# top.net
KiCad netlist of a schematic drawn in EAGLE
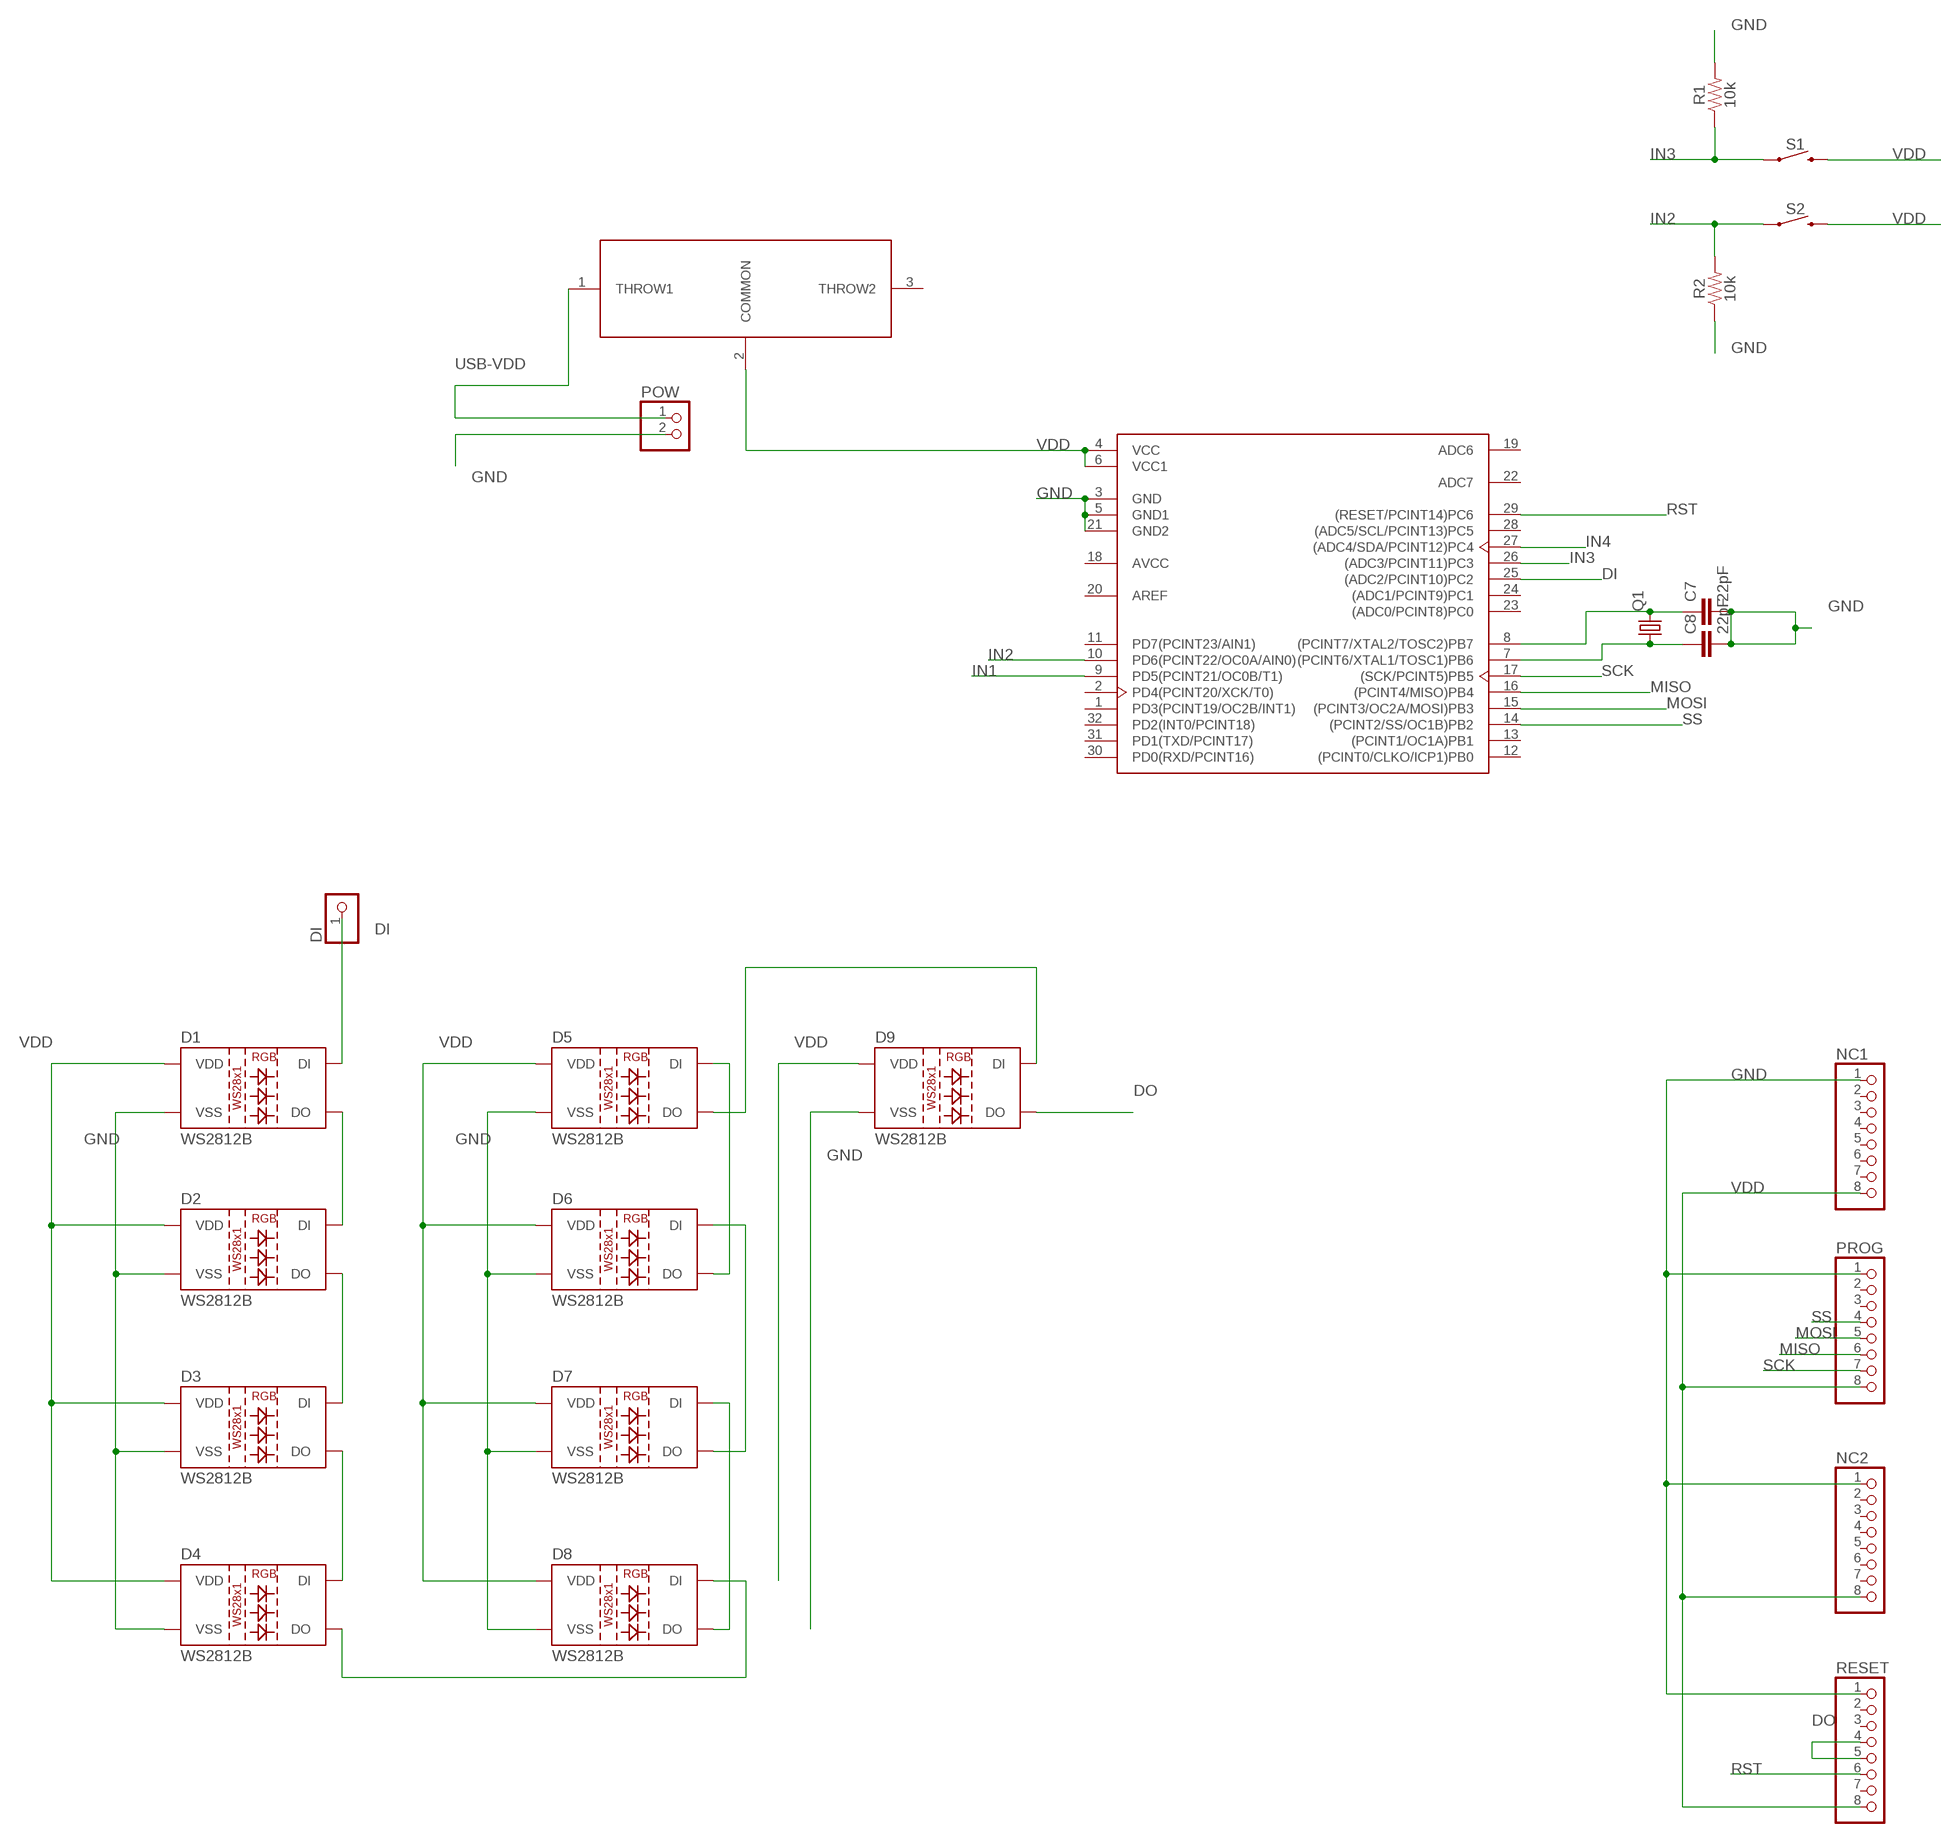
[diagram p0: schematic, sheet 1]

(export (version "E")
  (design (tool "Eeschema 10.0.6"))
  (components
    (comp (ref "C7")
      (value "22pF")
      (footprint "eagle-import:0805")
      (libsource (lib "eagle-import") (part "1.0UF-0805-25V-(+80/-20%)"))
    )
    (comp (ref "C8")
      (value "22pF")
      (footprint "eagle-import:0805")
      (libsource (lib "eagle-import") (part "1.0UF-0805-25V-(+80/-20%)"))
    )
    (comp (ref "D1")
      (value "WS2812B")
      (footprint "eagle-import:WS2812B")
      (libsource (lib "eagle-import") (part "WS2812B"))
    )
    (comp (ref "D2")
      (value "WS2812B")
      (footprint "eagle-import:WS2812B")
      (libsource (lib "eagle-import") (part "WS2812B"))
    )
    (comp (ref "D3")
      (value "WS2812B")
      (footprint "eagle-import:WS2812B")
      (libsource (lib "eagle-import") (part "WS2812B"))
    )
    (comp (ref "D4")
      (value "WS2812B")
      (footprint "eagle-import:WS2812B")
      (libsource (lib "eagle-import") (part "WS2812B"))
    )
    (comp (ref "D5")
      (value "WS2812B")
      (footprint "eagle-import:WS2812B")
      (libsource (lib "eagle-import") (part "WS2812B"))
    )
    (comp (ref "D6")
      (value "WS2812B")
      (footprint "eagle-import:WS2812B")
      (libsource (lib "eagle-import") (part "WS2812B"))
    )
    (comp (ref "D7")
      (value "WS2812B")
      (footprint "eagle-import:WS2812B")
      (libsource (lib "eagle-import") (part "WS2812B"))
    )
    (comp (ref "D8")
      (value "WS2812B")
      (footprint "eagle-import:WS2812B")
      (libsource (lib "eagle-import") (part "WS2812B"))
    )
    (comp (ref "D9")
      (value "WS2812B")
      (footprint "eagle-import:WS2812B")
      (libsource (lib "eagle-import") (part "WS2812B"))
    )
    (comp (ref "DI")
      (value "PINHD-1X1")
      (footprint "eagle-import:1X01")
      (libsource (lib "eagle-import") (part "PINHD-1X1"))
    )
    (comp (ref "IC1")
      (value "ATMEGA328P-AU")
      (footprint "eagle-import:TQFP-32")
      (fields
        (field (name "DIGIKEY_PART_NUMBER") "ATMEGA328P-AU-ND")
        (field (name "MANUFACTURER") "Microchip Technology")
        (field (name "CREATED_BY") "PCBLayout.com")
      )
      (libsource (lib "eagle-import") (part "ATMEGA328P-AU"))
    )
    (comp (ref "NC1")
      (value "PINHD-1X8")
      (footprint "eagle-import:1X08")
      (libsource (lib "eagle-import") (part "PINHD-1X8"))
    )
    (comp (ref "NC2")
      (value "PINHD-1X8")
      (footprint "eagle-import:1X08")
      (libsource (lib "eagle-import") (part "PINHD-1X8"))
    )
    (comp (ref "POW")
      (value "PINHD-1X2")
      (footprint "eagle-import:1X02")
      (libsource (lib "eagle-import") (part "PINHD-1X2"))
    )
    (comp (ref "PROG")
      (value "PINHD-1X8")
      (footprint "eagle-import:1X08")
      (libsource (lib "eagle-import") (part "PINHD-1X8"))
    )
    (comp (ref "Q1")
      (value "CRYSTALHC49S")
      (footprint "eagle-import:HC49_S")
      (libsource (lib "eagle-import") (part "CRYSTALHC49S"))
    )
    (comp (ref "R1")
      (value "10k")
      (footprint "eagle-import:0805")
      (libsource (lib "eagle-import") (part "0.3OHM-0805-1/8W-1%"))
    )
    (comp (ref "R2")
      (value "10k")
      (footprint "eagle-import:0805")
      (libsource (lib "eagle-import") (part "0.3OHM-0805-1/8W-1%"))
    )
    (comp (ref "RESET")
      (value "PINHD-1X8")
      (footprint "eagle-import:1X08")
      (libsource (lib "eagle-import") (part "PINHD-1X8"))
    )
    (comp (ref "S1")
      (value "MOMENTARY-SWITCH-SPST-PTH-6.0MM")
      (footprint "eagle-import:TACTILE_SWITCH_PTH_6.0MM")
      (libsource (lib "eagle-import") (part "MOMENTARY-SWITCH-SPST-PTH-6.0MM"))
    )
    (comp (ref "S2")
      (value "MOMENTARY-SWITCH-SPST-PTH-6.0MM")
      (footprint "eagle-import:TACTILE_SWITCH_PTH_6.0MM")
      (libsource (lib "eagle-import") (part "MOMENTARY-SWITCH-SPST-PTH-6.0MM"))
    )
    (comp (ref "U$2")
      (value "SLIDE_SWITCH_1P2T")
      (footprint "eagle-import:SLIDE_SWITCH_1P2T")
      (libsource (lib "eagle-import") (part "SLIDE_SWITCH_1P2T"))
    )
  )
  (nets
    (net (code "1") (name "/AREF") (class "Default")
      (node (ref "IC1") (pin "20") (pinfunction "AREF_20") (pintype "power_in"))
    )
    (net (code "2") (name "/AVCC") (class "Default")
      (node (ref "IC1") (pin "18") (pinfunction "AVCC_18") (pintype "power_in"))
    )
    (net (code "3") (name "/DI") (class "Default")
      (node (ref "D1") (pin "4") (pinfunction "DI_4") (pintype "bidirectional"))
      (node (ref "DI") (pin "1") (pinfunction "1_1") (pintype "passive"))
      (node (ref "IC1") (pin "25") (pinfunction "(ADC2/PCINT10)PC2_25") (pintype "bidirectional"))
    )
    (net (code "4") (name "/DO") (class "Default")
      (node (ref "D9") (pin "2") (pinfunction "DO_2") (pintype "bidirectional"))
      (node (ref "RESET") (pin "4") (pinfunction "4_4") (pintype "passive"))
      (node (ref "RESET") (pin "5") (pinfunction "5_5") (pintype "passive"))
    )
    (net (code "5") (name "/GND") (class "Default")
      (node (ref "C7") (pin "2") (pinfunction "2_2") (pintype "passive"))
      (node (ref "C8") (pin "2") (pinfunction "2_2") (pintype "passive"))
      (node (ref "D1") (pin "3") (pinfunction "VSS_3") (pintype "bidirectional"))
      (node (ref "D2") (pin "3") (pinfunction "VSS_3") (pintype "bidirectional"))
      (node (ref "D3") (pin "3") (pinfunction "VSS_3") (pintype "bidirectional"))
      (node (ref "D4") (pin "3") (pinfunction "VSS_3") (pintype "bidirectional"))
      (node (ref "D5") (pin "3") (pinfunction "VSS_3") (pintype "bidirectional"))
      (node (ref "D6") (pin "3") (pinfunction "VSS_3") (pintype "bidirectional"))
      (node (ref "D7") (pin "3") (pinfunction "VSS_3") (pintype "bidirectional"))
      (node (ref "D8") (pin "3") (pinfunction "VSS_3") (pintype "bidirectional"))
      (node (ref "D9") (pin "3") (pinfunction "VSS_3") (pintype "bidirectional"))
      (node (ref "IC1") (pin "21") (pinfunction "GND2_21") (pintype "power_in"))
      (node (ref "IC1") (pin "3") (pinfunction "GND_3") (pintype "power_in"))
      (node (ref "IC1") (pin "5") (pinfunction "GND1_5") (pintype "power_in"))
      (node (ref "NC1") (pin "1") (pinfunction "1_1") (pintype "passive"))
      (node (ref "NC2") (pin "1") (pinfunction "1_1") (pintype "passive"))
      (node (ref "POW") (pin "2") (pinfunction "2_2") (pintype "passive"))
      (node (ref "PROG") (pin "1") (pinfunction "1_1") (pintype "passive"))
      (node (ref "R1") (pin "2") (pinfunction "2_2") (pintype "passive"))
      (node (ref "R2") (pin "1") (pinfunction "1_1") (pintype "passive"))
      (node (ref "RESET") (pin "1") (pinfunction "1_1") (pintype "passive"))
    )
    (net (code "6") (name "/IN1") (class "Default")
      (node (ref "IC1") (pin "9") (pinfunction "PD5(PCINT21/OC0B/T1)_9") (pintype "bidirectional"))
    )
    (net (code "7") (name "/IN2") (class "Default")
      (node (ref "IC1") (pin "10") (pinfunction "PD6(PCINT22/OC0A/AIN0)_10") (pintype "bidirectional"))
      (node (ref "R2") (pin "2") (pinfunction "2_2") (pintype "passive"))
      (node (ref "S2") (pin "1") (pinfunction "1_1") (pintype "passive"))
    )
    (net (code "8") (name "/IN3") (class "Default")
      (node (ref "IC1") (pin "26") (pinfunction "(ADC3/PCINT11)PC3_26") (pintype "bidirectional"))
      (node (ref "R1") (pin "1") (pinfunction "1_1") (pintype "passive"))
      (node (ref "S1") (pin "1") (pinfunction "1_1") (pintype "passive"))
    )
    (net (code "9") (name "/IN4") (class "Default")
      (node (ref "IC1") (pin "27") (pinfunction "(ADC4/SDA/PCINT12)PC4_27") (pintype "bidirectional"))
    )
    (net (code "10") (name "/MISO") (class "Default")
      (node (ref "IC1") (pin "16") (pinfunction "(PCINT4/MISO)PB4_16") (pintype "bidirectional"))
      (node (ref "PROG") (pin "6") (pinfunction "6_6") (pintype "passive"))
    )
    (net (code "11") (name "/MOSI") (class "Default")
      (node (ref "IC1") (pin "15") (pinfunction "(PCINT3/OC2A/MOSI)PB3_15") (pintype "bidirectional"))
      (node (ref "PROG") (pin "5") (pinfunction "5_5") (pintype "passive"))
    )
    (net (code "12") (name "/RST") (class "Default")
      (node (ref "IC1") (pin "29") (pinfunction "(RESET/PCINT14)PC6_29") (pintype "bidirectional"))
      (node (ref "RESET") (pin "6") (pinfunction "6_6") (pintype "passive"))
    )
    (net (code "13") (name "/SCK") (class "Default")
      (node (ref "IC1") (pin "17") (pinfunction "(SCK/PCINT5)PB5_17") (pintype "bidirectional"))
      (node (ref "PROG") (pin "7") (pinfunction "7_7") (pintype "passive"))
    )
    (net (code "14") (name "/SS") (class "Default")
      (node (ref "IC1") (pin "14") (pinfunction "(PCINT2/SS/OC1B)PB2_14") (pintype "bidirectional"))
      (node (ref "PROG") (pin "4") (pinfunction "4_4") (pintype "passive"))
    )
    (net (code "15") (name "/USB-VDD") (class "Default")
      (node (ref "POW") (pin "1") (pinfunction "1_1") (pintype "passive"))
      (node (ref "U$2") (pin "1") (pinfunction "THROW1_1") (pintype "bidirectional"))
    )
    (net (code "16") (name "/VDD") (class "Default")
      (node (ref "D1") (pin "1") (pinfunction "VDD_1") (pintype "bidirectional"))
      (node (ref "D2") (pin "1") (pinfunction "VDD_1") (pintype "bidirectional"))
      (node (ref "D3") (pin "1") (pinfunction "VDD_1") (pintype "bidirectional"))
      (node (ref "D4") (pin "1") (pinfunction "VDD_1") (pintype "bidirectional"))
      (node (ref "D5") (pin "1") (pinfunction "VDD_1") (pintype "bidirectional"))
      (node (ref "D6") (pin "1") (pinfunction "VDD_1") (pintype "bidirectional"))
      (node (ref "D7") (pin "1") (pinfunction "VDD_1") (pintype "bidirectional"))
      (node (ref "D8") (pin "1") (pinfunction "VDD_1") (pintype "bidirectional"))
      (node (ref "D9") (pin "1") (pinfunction "VDD_1") (pintype "bidirectional"))
      (node (ref "IC1") (pin "4") (pinfunction "VCC_4") (pintype "power_in"))
      (node (ref "IC1") (pin "6") (pinfunction "VCC1_6") (pintype "power_in"))
      (node (ref "NC1") (pin "8") (pinfunction "8_8") (pintype "passive"))
      (node (ref "NC2") (pin "8") (pinfunction "8_8") (pintype "passive"))
      (node (ref "PROG") (pin "8") (pinfunction "8_8") (pintype "passive"))
      (node (ref "RESET") (pin "8") (pinfunction "8_8") (pintype "passive"))
      (node (ref "S1") (pin "3") (pinfunction "2_3") (pintype "passive"))
      (node (ref "S2") (pin "3") (pinfunction "2_3") (pintype "passive"))
      (node (ref "U$2") (pin "2") (pinfunction "COMMON_2") (pintype "bidirectional"))
    )
    (net (code "17") (name "Net-(D1-DO)") (class "Default")
      (node (ref "D1") (pin "2") (pinfunction "DO_2") (pintype "bidirectional"))
      (node (ref "D2") (pin "4") (pinfunction "DI_4") (pintype "bidirectional"))
    )
    (net (code "18") (name "Net-(D2-DO)") (class "Default")
      (node (ref "D2") (pin "2") (pinfunction "DO_2") (pintype "bidirectional"))
      (node (ref "D3") (pin "4") (pinfunction "DI_4") (pintype "bidirectional"))
    )
    (net (code "19") (name "Net-(D3-DO)") (class "Default")
      (node (ref "D3") (pin "2") (pinfunction "DO_2") (pintype "bidirectional"))
      (node (ref "D4") (pin "4") (pinfunction "DI_4") (pintype "bidirectional"))
    )
    (net (code "20") (name "Net-(D4-DO)") (class "Default")
      (node (ref "D4") (pin "2") (pinfunction "DO_2") (pintype "bidirectional"))
      (node (ref "D8") (pin "4") (pinfunction "DI_4") (pintype "bidirectional"))
    )
    (net (code "21") (name "Net-(D5-DI)") (class "Default")
      (node (ref "D5") (pin "4") (pinfunction "DI_4") (pintype "bidirectional"))
      (node (ref "D6") (pin "2") (pinfunction "DO_2") (pintype "bidirectional"))
    )
    (net (code "22") (name "Net-(D5-DO)") (class "Default")
      (node (ref "D5") (pin "2") (pinfunction "DO_2") (pintype "bidirectional"))
      (node (ref "D9") (pin "4") (pinfunction "DI_4") (pintype "bidirectional"))
    )
    (net (code "23") (name "Net-(D6-DI)") (class "Default")
      (node (ref "D6") (pin "4") (pinfunction "DI_4") (pintype "bidirectional"))
      (node (ref "D7") (pin "2") (pinfunction "DO_2") (pintype "bidirectional"))
    )
    (net (code "24") (name "Net-(D7-DI)") (class "Default")
      (node (ref "D7") (pin "4") (pinfunction "DI_4") (pintype "bidirectional"))
      (node (ref "D8") (pin "2") (pinfunction "DO_2") (pintype "bidirectional"))
    )
    (net (code "25") (name "Net-(IC1-(PCINT6{slash}XTAL1{slash}TOSC1)PB6)") (class "Default")
      (node (ref "C8") (pin "1") (pinfunction "1_1") (pintype "passive"))
      (node (ref "IC1") (pin "7") (pinfunction "(PCINT6/XTAL1/TOSC1)PB6_7") (pintype "bidirectional"))
      (node (ref "Q1") (pin "1") (pinfunction "1_1") (pintype "passive"))
    )
    (net (code "26") (name "Net-(IC1-(PCINT7{slash}XTAL2{slash}TOSC2)PB7)") (class "Default")
      (node (ref "C7") (pin "1") (pinfunction "1_1") (pintype "passive"))
      (node (ref "IC1") (pin "8") (pinfunction "(PCINT7/XTAL2/TOSC2)PB7_8") (pintype "bidirectional"))
      (node (ref "Q1") (pin "2") (pinfunction "2_2") (pintype "passive"))
    )
    (net (code "27") (name "unconnected-(IC1-(ADC0{slash}PCINT8)PC0-Pad23)") (class "Default")
      (node (ref "IC1") (pin "23") (pinfunction "(ADC0/PCINT8)PC0_23") (pintype "bidirectional"))
    )
    (net (code "28") (name "unconnected-(IC1-(ADC1{slash}PCINT9)PC1-Pad24)") (class "Default")
      (node (ref "IC1") (pin "24") (pinfunction "(ADC1/PCINT9)PC1_24") (pintype "bidirectional"))
    )
    (net (code "29") (name "unconnected-(IC1-(ADC5{slash}SCL{slash}PCINT13)PC5-Pad28)") (class "Default")
      (node (ref "IC1") (pin "28") (pinfunction "(ADC5/SCL/PCINT13)PC5_28") (pintype "bidirectional"))
    )
    (net (code "30") (name "unconnected-(IC1-(PCINT0{slash}CLKO{slash}ICP1)PB0-Pad12)") (class "Default")
      (node (ref "IC1") (pin "12") (pinfunction "(PCINT0/CLKO/ICP1)PB0_12") (pintype "bidirectional"))
    )
    (net (code "31") (name "unconnected-(IC1-(PCINT1{slash}OC1A)PB1-Pad13)") (class "Default")
      (node (ref "IC1") (pin "13") (pinfunction "(PCINT1/OC1A)PB1_13") (pintype "bidirectional"))
    )
    (net (code "32") (name "unconnected-(IC1-ADC6-Pad19)") (class "Default")
      (node (ref "IC1") (pin "19") (pinfunction "ADC6_19") (pintype "input"))
    )
    (net (code "33") (name "unconnected-(IC1-ADC7-Pad22)") (class "Default")
      (node (ref "IC1") (pin "22") (pinfunction "ADC7_22") (pintype "input"))
    )
    (net (code "34") (name "unconnected-(IC1-PD0(RXD{slash}PCINT16)-Pad30)") (class "Default")
      (node (ref "IC1") (pin "30") (pinfunction "PD0(RXD/PCINT16)_30") (pintype "bidirectional"))
    )
    (net (code "35") (name "unconnected-(IC1-PD1(TXD{slash}PCINT17)-Pad31)") (class "Default")
      (node (ref "IC1") (pin "31") (pinfunction "PD1(TXD/PCINT17)_31") (pintype "bidirectional"))
    )
    (net (code "36") (name "unconnected-(IC1-PD2(INT0{slash}PCINT18)-Pad32)") (class "Default")
      (node (ref "IC1") (pin "32") (pinfunction "PD2(INT0/PCINT18)_32") (pintype "bidirectional"))
    )
    (net (code "37") (name "unconnected-(IC1-PD3(PCINT19{slash}OC2B{slash}INT1)-Pad1)") (class "Default")
      (node (ref "IC1") (pin "1") (pinfunction "PD3(PCINT19/OC2B/INT1)_1") (pintype "bidirectional"))
    )
    (net (code "38") (name "unconnected-(IC1-PD4(PCINT20{slash}XCK{slash}T0)-Pad2)") (class "Default")
      (node (ref "IC1") (pin "2") (pinfunction "PD4(PCINT20/XCK/T0)_2") (pintype "bidirectional"))
    )
    (net (code "39") (name "unconnected-(IC1-PD7(PCINT23{slash}AIN1)-Pad11)") (class "Default")
      (node (ref "IC1") (pin "11") (pinfunction "PD7(PCINT23/AIN1)_11") (pintype "bidirectional"))
    )
    (net (code "40") (name "unconnected-(NC1-Pad2)") (class "Default")
      (node (ref "NC1") (pin "2") (pinfunction "2_2") (pintype "passive"))
    )
    (net (code "41") (name "unconnected-(NC1-Pad3)") (class "Default")
      (node (ref "NC1") (pin "3") (pinfunction "3_3") (pintype "passive"))
    )
    (net (code "42") (name "unconnected-(NC1-Pad4)") (class "Default")
      (node (ref "NC1") (pin "4") (pinfunction "4_4") (pintype "passive"))
    )
    (net (code "43") (name "unconnected-(NC1-Pad5)") (class "Default")
      (node (ref "NC1") (pin "5") (pinfunction "5_5") (pintype "passive"))
    )
    (net (code "44") (name "unconnected-(NC1-Pad6)") (class "Default")
      (node (ref "NC1") (pin "6") (pinfunction "6_6") (pintype "passive"))
    )
    (net (code "45") (name "unconnected-(NC1-Pad7)") (class "Default")
      (node (ref "NC1") (pin "7") (pinfunction "7_7") (pintype "passive"))
    )
    (net (code "46") (name "unconnected-(NC2-Pad2)") (class "Default")
      (node (ref "NC2") (pin "2") (pinfunction "2_2") (pintype "passive"))
    )
    (net (code "47") (name "unconnected-(NC2-Pad3)") (class "Default")
      (node (ref "NC2") (pin "3") (pinfunction "3_3") (pintype "passive"))
    )
    (net (code "48") (name "unconnected-(NC2-Pad4)") (class "Default")
      (node (ref "NC2") (pin "4") (pinfunction "4_4") (pintype "passive"))
    )
    (net (code "49") (name "unconnected-(NC2-Pad5)") (class "Default")
      (node (ref "NC2") (pin "5") (pinfunction "5_5") (pintype "passive"))
    )
    (net (code "50") (name "unconnected-(NC2-Pad6)") (class "Default")
      (node (ref "NC2") (pin "6") (pinfunction "6_6") (pintype "passive"))
    )
    (net (code "51") (name "unconnected-(NC2-Pad7)") (class "Default")
      (node (ref "NC2") (pin "7") (pinfunction "7_7") (pintype "passive"))
    )
    (net (code "52") (name "unconnected-(PROG-Pad2)") (class "Default")
      (node (ref "PROG") (pin "2") (pinfunction "2_2") (pintype "passive"))
    )
    (net (code "53") (name "unconnected-(PROG-Pad3)") (class "Default")
      (node (ref "PROG") (pin "3") (pinfunction "3_3") (pintype "passive"))
    )
    (net (code "54") (name "unconnected-(RESET-Pad2)") (class "Default")
      (node (ref "RESET") (pin "2") (pinfunction "2_2") (pintype "passive"))
    )
    (net (code "55") (name "unconnected-(RESET-Pad3)") (class "Default")
      (node (ref "RESET") (pin "3") (pinfunction "3_3") (pintype "passive"))
    )
    (net (code "56") (name "unconnected-(RESET-Pad7)") (class "Default")
      (node (ref "RESET") (pin "7") (pinfunction "7_7") (pintype "passive"))
    )
    (net (code "57") (name "unconnected-(U$2-THROW2-Pad3)") (class "Default")
      (node (ref "U$2") (pin "3") (pinfunction "THROW2_3") (pintype "bidirectional"))
    )
  )
)
